# v1_0.net
KiCad netlist of a schematic drawn in Altium Designer
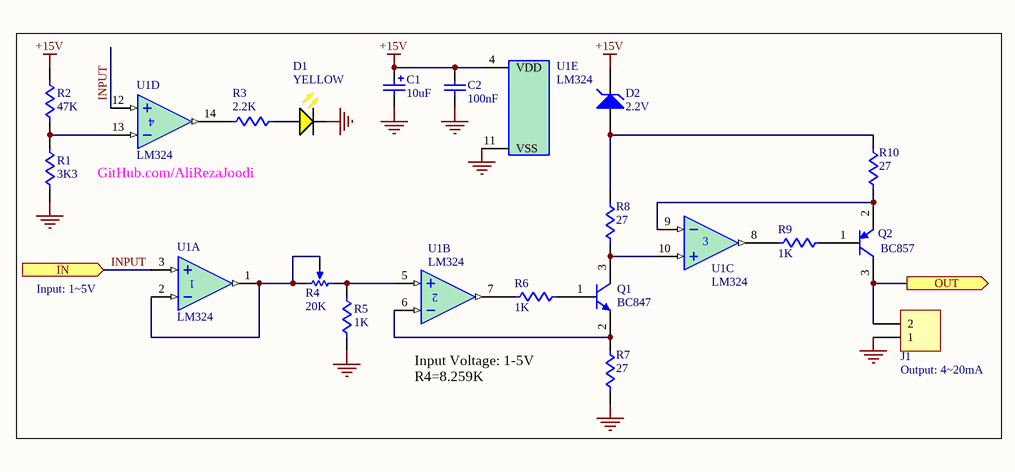
[diagram p0: v1.0.SchDoc]

(export (version "E")
  (design (tool "Eeschema 10.0.6"))
  (components
    (comp (ref "C1")
      (value "10uF")
      (footprint "Cap_B")
      (description "Polarized Capacitor (Radial)")
      (fields
        (field (name "MANUFACTURER") "Generic Components")
        (field (name "Comment") "Capacitor")
        (field (name "PUBLISHER") "Altium Limited")
      )
      (libsource (lib "Miscellaneous Devices") (part "Cap Pol1"))
    )
    (comp (ref "C2")
      (value "100nF")
      (footprint "0805")
      (description "Capacitor")
      (fields
        (field (name "MANUFACTURER") "Generic Components")
        (field (name "Comment") "Cap")
        (field (name "PUBLISHER") "Altium Limited")
      )
      (libsource (lib "Miscellaneous Devices") (part "Cap"))
    )
    (comp (ref "D1")
      (value "YELLOW")
      (footprint "LED_THD_3MM_YELLOW_R")
      (description "LED, Yellow")
      (fields (field (name "MANUFACTURER") "Generic Components") (field (name "PUBLISHER") "Altium Limited"))
      (libsource (lib "Display") (part "LED_YELLOW"))
    )
    (comp (ref "D2")
      (value "2.2V")
      (footprint "MELF-D3516-1406")
      (description "Zener Diode")
      (fields
        (field (name "MANUFACTURER") "Generic Components")
        (field (name "Comment") "LED")
        (field (name "PUBLISHER") "Altium Limited")
      )
      (libsource (lib "Miscellaneous Devices") (part "D Zener"))
    )
    (comp (ref "J1")
      (value "J17")
      (footprint "Fonics_2PIN_1")
      (description "Header, 2-Pin")
      (fields (field (name "PUBLISHER") "Altium Limited"))
      (libsource (lib "Miscellaneous Connectors") (part "Header 2"))
    )
    (comp (ref "Q1")
      (value "BC847")
      (footprint "SOT23-3N")
      (description "Silicon Bipolar Transistor")
      (fields (field (name "Comment") "NPN"))
      (libsource (lib "my Libraries") (part "BC847"))
    )
    (comp (ref "Q2")
      (value "BC857")
      (footprint "SOT23-3N")
      (description "Silicon Bipolar Transistor")
      (fields (field (name "Comment") "Q"))
      (libsource (lib "my Libraries") (part "BC857"))
    )
    (comp (ref "R1")
      (value "3K3")
      (footprint "0805")
      (description "Resistor")
      (fields (field (name "MANUFACTURER") "Generic Components") (field (name "PUBLISHER") "Altium Limited"))
      (libsource (lib "Miscellaneous Devices") (part "Res1"))
    )
    (comp (ref "R2")
      (value "47K")
      (footprint "0805")
      (description "Resistor")
      (fields
        (field (name "MANUFACTURER") "Generic Components")
        (field (name "Comment") "Res")
        (field (name "PUBLISHER") "Altium Limited")
      )
      (libsource (lib "Miscellaneous Devices") (part "Res1"))
    )
    (comp (ref "R3")
      (value "2.2K")
      (footprint "0805")
      (description "Resistor")
      (fields
        (field (name "MANUFACTURER") "Generic Components")
        (field (name "Comment") "Res")
        (field (name "PUBLISHER") "Altium Limited")
      )
      (libsource (lib "Miscellaneous Devices") (part "Res1"))
    )
    (comp (ref "R4")
      (value "20K")
      (footprint "VR4_")
      (description "Potentiometer")
      (fields
        (field (name "MANUFACTURER") "Generic Components")
        (field (name "Comment") "RES")
        (field (name "PUBLISHER") "Altium Limited")
      )
      (libsource (lib "my Libraries") (part "RPot1"))
    )
    (comp (ref "R5")
      (value "1K")
      (footprint "0805")
      (description "Resistor")
      (fields
        (field (name "MANUFACTURER") "Generic Components")
        (field (name "Comment") "RES")
        (field (name "PUBLISHER") "Altium Limited")
      )
      (libsource (lib "Miscellaneous Devices") (part "Res1"))
    )
    (comp (ref "R6")
      (value "1K")
      (footprint "0805")
      (description "Resistor")
      (fields
        (field (name "MANUFACTURER") "Generic Components")
        (field (name "Comment") "RES")
        (field (name "PUBLISHER") "Altium Limited")
      )
      (libsource (lib "Miscellaneous Devices") (part "Res1"))
    )
    (comp (ref "R7")
      (value "27")
      (footprint "0805")
      (description "Resistor")
      (fields
        (field (name "MANUFACTURER") "Generic Components")
        (field (name "Comment") "R59")
        (field (name "PUBLISHER") "Altium Limited")
      )
      (libsource (lib "Miscellaneous Devices") (part "Res1"))
    )
    (comp (ref "R8")
      (value "27")
      (footprint "0805")
      (description "Resistor")
      (fields
        (field (name "MANUFACTURER") "Generic Components")
        (field (name "Comment") "R58")
        (field (name "PUBLISHER") "Altium Limited")
      )
      (libsource (lib "Miscellaneous Devices") (part "Res1"))
    )
    (comp (ref "R9")
      (value "1K")
      (footprint "0805")
      (description "Resistor")
      (fields
        (field (name "MANUFACTURER") "Generic Components")
        (field (name "Comment") "R61")
        (field (name "PUBLISHER") "Altium Limited")
      )
      (libsource (lib "Miscellaneous Devices") (part "Res1"))
    )
    (comp (ref "R10")
      (value "27")
      (footprint "0805")
      (description "Resistor")
      (fields
        (field (name "MANUFACTURER") "Generic Components")
        (field (name "Comment") "R60")
        (field (name "PUBLISHER") "Altium Limited")
      )
      (libsource (lib "Miscellaneous Devices") (part "Res1"))
    )
    (comp (ref "U1")
      (value "LM324")
      (footprint "DIP_14")
      (description "Quad Low-Power Operational Amplifier")
      (fields (field (name "PUBLISHER") "Altium Limited"))
      (libsource (lib "") (part "LM324_1"))
    )
  )
  (nets
    (net (code "1") (name "+15V") (class "Default")
      (node (ref "C1") (pin "1") (pinfunction "1_1") (pintype "passive"))
      (node (ref "C2") (pin "2") (pinfunction "2_2") (pintype "passive"))
      (node (ref "D2") (pin "2") (pinfunction "K_2") (pintype "passive"))
      (node (ref "R2") (pin "1") (pinfunction "1_1") (pintype "passive"))
      (node (ref "U1") (pin "4") (pinfunction "VDD_4") (pintype "passive"))
    )
    (net (code "2") (name "/INPUT") (class "Default")
      (node (ref "U1") (pin "12") (pinfunction "IN+_12") (pintype "input"))
      (node (ref "U1") (pin "3") (pinfunction "IN+_3") (pintype "input"))
    )
    (net (code "3") (name "/OUT") (class "Default")
      (node (ref "J1") (pin "2") (pinfunction "2_2") (pintype "passive"))
      (node (ref "Q2") (pin "3") (pinfunction "C_3") (pintype "passive"))
    )
    (net (code "4") (name "GND") (class "Default")
      (node (ref "C1") (pin "2") (pinfunction "2_2") (pintype "passive"))
      (node (ref "C2") (pin "1") (pinfunction "1_1") (pintype "passive"))
      (node (ref "D1") (pin "2") (pinfunction "K_2") (pintype "passive"))
      (node (ref "J1") (pin "1") (pinfunction "1_1") (pintype "passive"))
      (node (ref "R1") (pin "2") (pinfunction "2_2") (pintype "passive"))
      (node (ref "R5") (pin "2") (pinfunction "2_2") (pintype "passive"))
      (node (ref "R7") (pin "1") (pinfunction "1_1") (pintype "passive"))
      (node (ref "U1") (pin "11") (pinfunction "VSS_11") (pintype "power_in"))
    )
    (net (code "5") (name "Net-(D1-A)") (class "Default")
      (node (ref "D1") (pin "1") (pinfunction "A_1") (pintype "passive"))
      (node (ref "R3") (pin "1") (pinfunction "1_1") (pintype "passive"))
    )
    (net (code "6") (name "Net-(D2-A)") (class "Default")
      (node (ref "D2") (pin "1") (pinfunction "A_1") (pintype "passive"))
      (node (ref "R10") (pin "2") (pinfunction "2_2") (pintype "passive"))
      (node (ref "R8") (pin "2") (pinfunction "2_2") (pintype "passive"))
    )
    (net (code "7") (name "Net-(Q1-B)") (class "Default")
      (node (ref "Q1") (pin "1") (pinfunction "B_1") (pintype "passive"))
      (node (ref "R6") (pin "2") (pinfunction "2_2") (pintype "passive"))
    )
    (net (code "8") (name "Net-(Q1-C)") (class "Default")
      (node (ref "Q1") (pin "3") (pinfunction "C_3") (pintype "passive"))
      (node (ref "R8") (pin "1") (pinfunction "1_1") (pintype "passive"))
      (node (ref "U1") (pin "10") (pinfunction "IN+_10") (pintype "input"))
    )
    (net (code "9") (name "Net-(Q1-E)") (class "Default")
      (node (ref "Q1") (pin "2") (pinfunction "E_2") (pintype "passive"))
      (node (ref "R7") (pin "2") (pinfunction "2_2") (pintype "passive"))
      (node (ref "U1") (pin "6") (pinfunction "IN-_6") (pintype "input"))
    )
    (net (code "10") (name "Net-(Q2-B)") (class "Default")
      (node (ref "Q2") (pin "1") (pinfunction "B_1") (pintype "passive"))
      (node (ref "R9") (pin "2") (pinfunction "2_2") (pintype "passive"))
    )
    (net (code "11") (name "Net-(Q2-E)") (class "Default")
      (node (ref "Q2") (pin "2") (pinfunction "E_2") (pintype "passive"))
      (node (ref "R10") (pin "1") (pinfunction "1_1") (pintype "passive"))
      (node (ref "U1") (pin "9") (pinfunction "IN-_9") (pintype "input"))
    )
    (net (code "12") (name "Net-(R4-BOT)") (class "Default")
      (node (ref "R4") (pin "2") (pinfunction "BOT_2") (pintype "passive"))
      (node (ref "R4") (pin "3") (pinfunction "TAP_3") (pintype "passive"))
      (node (ref "U1") (pin "1") (pinfunction "OUT_1") (pintype "output"))
      (node (ref "U1") (pin "2") (pinfunction "IN-_2") (pintype "input"))
    )
    (net (code "13") (name "Net-(R4-TOP)") (class "Default")
      (node (ref "R4") (pin "1") (pinfunction "TOP_1") (pintype "passive"))
      (node (ref "R5") (pin "1") (pinfunction "1_1") (pintype "passive"))
      (node (ref "U1") (pin "5") (pinfunction "IN+_5") (pintype "input"))
    )
    (net (code "14") (name "Net-(U1B-OUT)") (class "Default")
      (node (ref "R6") (pin "1") (pinfunction "1_1") (pintype "passive"))
      (node (ref "U1") (pin "7") (pinfunction "OUT_7") (pintype "output"))
    )
    (net (code "15") (name "Net-(U1C-OUT)") (class "Default")
      (node (ref "R9") (pin "1") (pinfunction "1_1") (pintype "passive"))
      (node (ref "U1") (pin "8") (pinfunction "OUT_8") (pintype "output"))
    )
    (net (code "16") (name "Net-(U1D-IN-)") (class "Default")
      (node (ref "R1") (pin "1") (pinfunction "1_1") (pintype "passive"))
      (node (ref "R2") (pin "2") (pinfunction "2_2") (pintype "passive"))
      (node (ref "U1") (pin "13") (pinfunction "IN-_13") (pintype "input"))
    )
    (net (code "17") (name "Net-(U1D-OUT)") (class "Default")
      (node (ref "R3") (pin "2") (pinfunction "2_2") (pintype "passive"))
      (node (ref "U1") (pin "14") (pinfunction "OUT_14") (pintype "output"))
    )
  )
)
